# AM-Crystal-RX-LM324.net
KiCad netlist of a schematic drawn in EAGLE
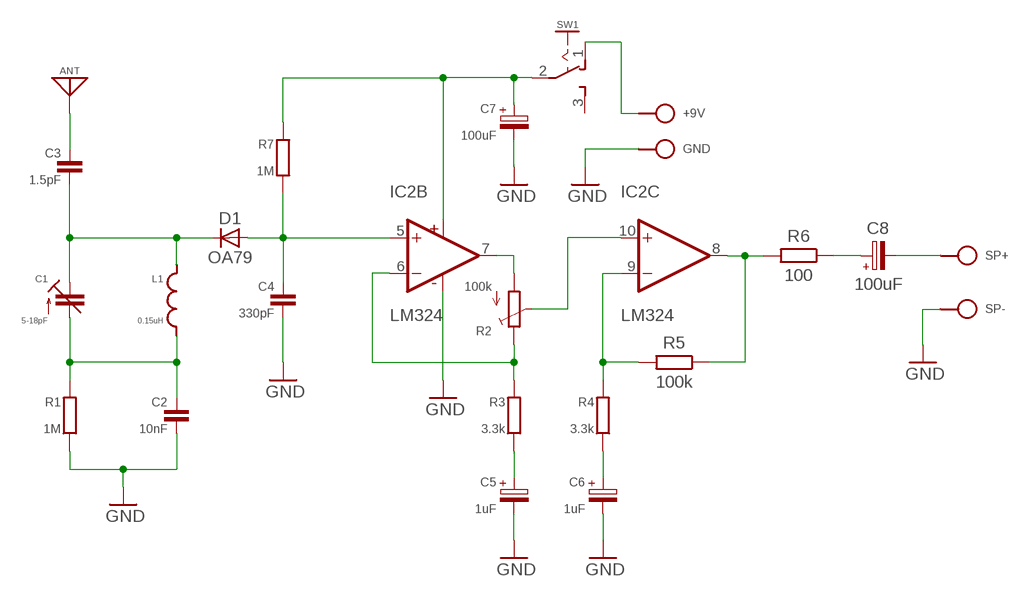
[diagram p0: schematic, sheet 1]

(export (version "E")
  (design (tool "Eeschema 10.0.6"))
  (components
    (comp (ref "+9V")
      (value "BAT+")
      (footprint "eagle-import:SPAD")
      (libsource (lib "eagle-import") (part "SPAD"))
    )
    (comp (ref "ANT")
      (value "ANT")
      (footprint "eagle-import:SPAD")
      (libsource (lib "eagle-import") (part "ANT"))
    )
    (comp (ref "C1")
      (value "5-18pF")
      (footprint "eagle-import:TRIM-2222-808")
      (libsource (lib "eagle-import") (part "C-TR-PH201272222-808-2PIN"))
    )
    (comp (ref "C2")
      (value "10nF")
      (footprint "eagle-import:C050-025X075_V")
      (libsource (lib "eagle-import") (part "C050-025X075/V"))
    )
    (comp (ref "C3")
      (value "1.5pF")
      (footprint "eagle-import:C050-020X036")
      (libsource (lib "eagle-import") (part "C050-020X036"))
    )
    (comp (ref "C4")
      (value "330pF")
      (footprint "eagle-import:C050-024X044_V")
      (libsource (lib "eagle-import") (part "C050-024X044/V"))
    )
    (comp (ref "C5")
      (value "1uF")
      (footprint "eagle-import:E2.5-4_V")
      (libsource (lib "eagle-import") (part "CPOLE2,5-4/V"))
    )
    (comp (ref "C6")
      (value "1uF")
      (footprint "eagle-import:E2,5-3_V")
      (libsource (lib "eagle-import") (part "CPOLE2,5-3/V"))
    )
    (comp (ref "C7")
      (value "100uF")
      (footprint "eagle-import:E5-5_V")
      (libsource (lib "eagle-import") (part "CPOLE5-5/V"))
    )
    (comp (ref "C8")
      (value "100uF")
      (footprint "eagle-import:E2,5-5_V")
      (libsource (lib "eagle-import") (part "CPOLE2,5-5/V"))
    )
    (comp (ref "D1")
      (value "OA79")
      (footprint "eagle-import:OA79-18_V")
      (libsource (lib "eagle-import") (part "OA7918/V"))
    )
    (comp (ref "GND")
      (value "BAT-")
      (footprint "eagle-import:SPAD")
      (libsource (lib "eagle-import") (part "SPAD"))
    )
    (comp (ref "IC2")
      (value "LM324")
      (footprint "eagle-import:DIL14")
      (libsource (lib "eagle-import") (part "LM324N"))
    )
    (comp (ref "L1")
      (value "0.15uH")
      (footprint "eagle-import:L-04-5_5")
      (libsource (lib "eagle-import") (part "L-SHORT04-5/5"))
    )
    (comp (ref "R1")
      (value "1M")
      (footprint "eagle-import:0202_7-V")
      (libsource (lib "eagle-import") (part "R0202/7-V"))
    )
    (comp (ref "R2")
      (value "100k")
      (footprint "eagle-import:B64Y")
      (libsource (lib "eagle-import") (part "TRIM"))
    )
    (comp (ref "R3")
      (value "3.3k")
      (footprint "eagle-import:0202_7")
      (libsource (lib "eagle-import") (part "R0202/7"))
    )
    (comp (ref "R4")
      (value "3.3k")
      (footprint "eagle-import:0202_7-V")
      (libsource (lib "eagle-import") (part "R0202/7-V"))
    )
    (comp (ref "R5")
      (value "100k")
      (footprint "eagle-import:0202_7-V")
      (libsource (lib "eagle-import") (part "R0202/7-V"))
    )
    (comp (ref "R6")
      (value "100")
      (footprint "eagle-import:0202_7-V")
      (libsource (lib "eagle-import") (part "R0202/7-V"))
    )
    (comp (ref "R7")
      (value "1M")
      (footprint "eagle-import:0202_7-V")
      (libsource (lib "eagle-import") (part "R0202/7-V"))
    )
    (comp (ref "SP+")
      (value "SPKR+")
      (footprint "eagle-import:SPAD")
      (libsource (lib "eagle-import") (part "SPAD"))
    )
    (comp (ref "SP-")
      (value "SPKR-")
      (footprint "eagle-import:SPAD")
      (libsource (lib "eagle-import") (part "SPAD"))
    )
    (comp (ref "SW1")
      (value "SL-SW-1P-2T-H")
      (footprint "eagle-import:SLSW-1P2T-H")
      (libsource (lib "eagle-import") (part "SL-SW-1P-2T-H"))
    )
  )
  (nets
    (net (code "1") (name "GND") (class "Default")
      (node (ref "C2") (pin "2") (pinfunction "2_2") (pintype "passive"))
      (node (ref "C4") (pin "2") (pinfunction "2_2") (pintype "passive"))
      (node (ref "C5") (pin "-") (pinfunction "-_-") (pintype "passive"))
      (node (ref "C6") (pin "-") (pinfunction "-_-") (pintype "passive"))
      (node (ref "C7") (pin "-") (pinfunction "-_-") (pintype "passive"))
      (node (ref "GND") (pin "1") (pinfunction "P$1_1") (pintype "passive"))
      (node (ref "IC2") (pin "11") (pinfunction "V-_11") (pintype "power_in"))
      (node (ref "R1") (pin "2") (pinfunction "2_2") (pintype "passive"))
      (node (ref "SP-") (pin "1") (pinfunction "P$1_1") (pintype "passive"))
    )
    (net (code "2") (name "Net-(+9V-P$1)") (class "Default")
      (node (ref "+9V") (pin "1") (pinfunction "P$1_1") (pintype "passive"))
      (node (ref "SW1") (pin "1") (pinfunction "O_1") (pintype "passive"))
    )
    (net (code "3") (name "Net-(ANT-Pad1)") (class "Default")
      (node (ref "ANT") (pin "1") (pinfunction "1_1") (pintype "output"))
      (node (ref "C3") (pin "1") (pinfunction "1_1") (pintype "passive"))
    )
    (net (code "4") (name "Net-(C1-A)") (class "Default")
      (node (ref "C1") (pin "1") (pinfunction "A_1") (pintype "passive"))
      (node (ref "C2") (pin "1") (pinfunction "1_1") (pintype "passive"))
      (node (ref "L1") (pin "1") (pinfunction "1_1") (pintype "passive"))
      (node (ref "R1") (pin "1") (pinfunction "1_1") (pintype "passive"))
    )
    (net (code "5") (name "Net-(C1-E)") (class "Default")
      (node (ref "C1") (pin "2") (pinfunction "E_2") (pintype "passive"))
      (node (ref "C3") (pin "2") (pinfunction "2_2") (pintype "passive"))
      (node (ref "D1") (pin "C") (pinfunction "C_C") (pintype "passive"))
      (node (ref "L1") (pin "2") (pinfunction "2_2") (pintype "passive"))
    )
    (net (code "6") (name "Net-(C5-Pad+)") (class "Default")
      (node (ref "C5") (pin "+") (pinfunction "+_+") (pintype "passive"))
      (node (ref "R3") (pin "2") (pinfunction "2_2") (pintype "passive"))
    )
    (net (code "7") (name "Net-(C6-Pad+)") (class "Default")
      (node (ref "C6") (pin "+") (pinfunction "+_+") (pintype "passive"))
      (node (ref "R4") (pin "2") (pinfunction "2_2") (pintype "passive"))
    )
    (net (code "8") (name "Net-(C8-Pad+)") (class "Default")
      (node (ref "C8") (pin "+") (pinfunction "+_+") (pintype "passive"))
      (node (ref "R6") (pin "2") (pinfunction "2_2") (pintype "passive"))
    )
    (net (code "9") (name "Net-(IC2B-+IN)") (class "Default")
      (node (ref "C4") (pin "1") (pinfunction "1_1") (pintype "passive"))
      (node (ref "D1") (pin "A") (pinfunction "A_A") (pintype "passive"))
      (node (ref "IC2") (pin "5") (pinfunction "+IN_5") (pintype "input"))
      (node (ref "R7") (pin "2") (pinfunction "2_2") (pintype "passive"))
    )
    (net (code "10") (name "Net-(IC2B--IN)") (class "Default")
      (node (ref "IC2") (pin "6") (pinfunction "-IN_6") (pintype "input"))
      (node (ref "R2") (pin "E") (pinfunction "E_E") (pintype "passive"))
      (node (ref "R3") (pin "1") (pinfunction "1_1") (pintype "passive"))
    )
    (net (code "11") (name "Net-(IC2B-OUT)") (class "Default")
      (node (ref "IC2") (pin "7") (pinfunction "OUT_7") (pintype "output"))
      (node (ref "R2") (pin "A") (pinfunction "A_A") (pintype "passive"))
    )
    (net (code "12") (name "Net-(IC2C-+IN)") (class "Default")
      (node (ref "IC2") (pin "10") (pinfunction "+IN_10") (pintype "input"))
      (node (ref "R2") (pin "S") (pinfunction "S_S") (pintype "passive"))
    )
    (net (code "13") (name "Net-(IC2C--IN)") (class "Default")
      (node (ref "IC2") (pin "9") (pinfunction "-IN_9") (pintype "input"))
      (node (ref "R4") (pin "1") (pinfunction "1_1") (pintype "passive"))
      (node (ref "R5") (pin "1") (pinfunction "1_1") (pintype "passive"))
    )
    (net (code "14") (name "Net-(IC2C-OUT)") (class "Default")
      (node (ref "IC2") (pin "8") (pinfunction "OUT_8") (pintype "output"))
      (node (ref "R5") (pin "2") (pinfunction "2_2") (pintype "passive"))
      (node (ref "R6") (pin "1") (pinfunction "1_1") (pintype "passive"))
    )
    (net (code "15") (name "Net-(IC2E-V+)") (class "Default")
      (node (ref "C7") (pin "+") (pinfunction "+_+") (pintype "passive"))
      (node (ref "IC2") (pin "4") (pinfunction "V+_4") (pintype "power_in"))
      (node (ref "R7") (pin "1") (pinfunction "1_1") (pintype "passive"))
      (node (ref "SW1") (pin "2") (pinfunction "P_2") (pintype "passive"))
    )
    (net (code "16") (name "Net-(SP+-P$1)") (class "Default")
      (node (ref "C8") (pin "-") (pinfunction "-_-") (pintype "passive"))
      (node (ref "SP+") (pin "1") (pinfunction "P$1_1") (pintype "passive"))
    )
    (net (code "17") (name "unconnected-(SW1-S-Pad3)") (class "Default")
      (node (ref "SW1") (pin "3") (pinfunction "S_3") (pintype "passive"))
    )
  )
)
